# Capacitive_Rain_Sensor.net
KiCad netlist of a schematic drawn in Altium Designer
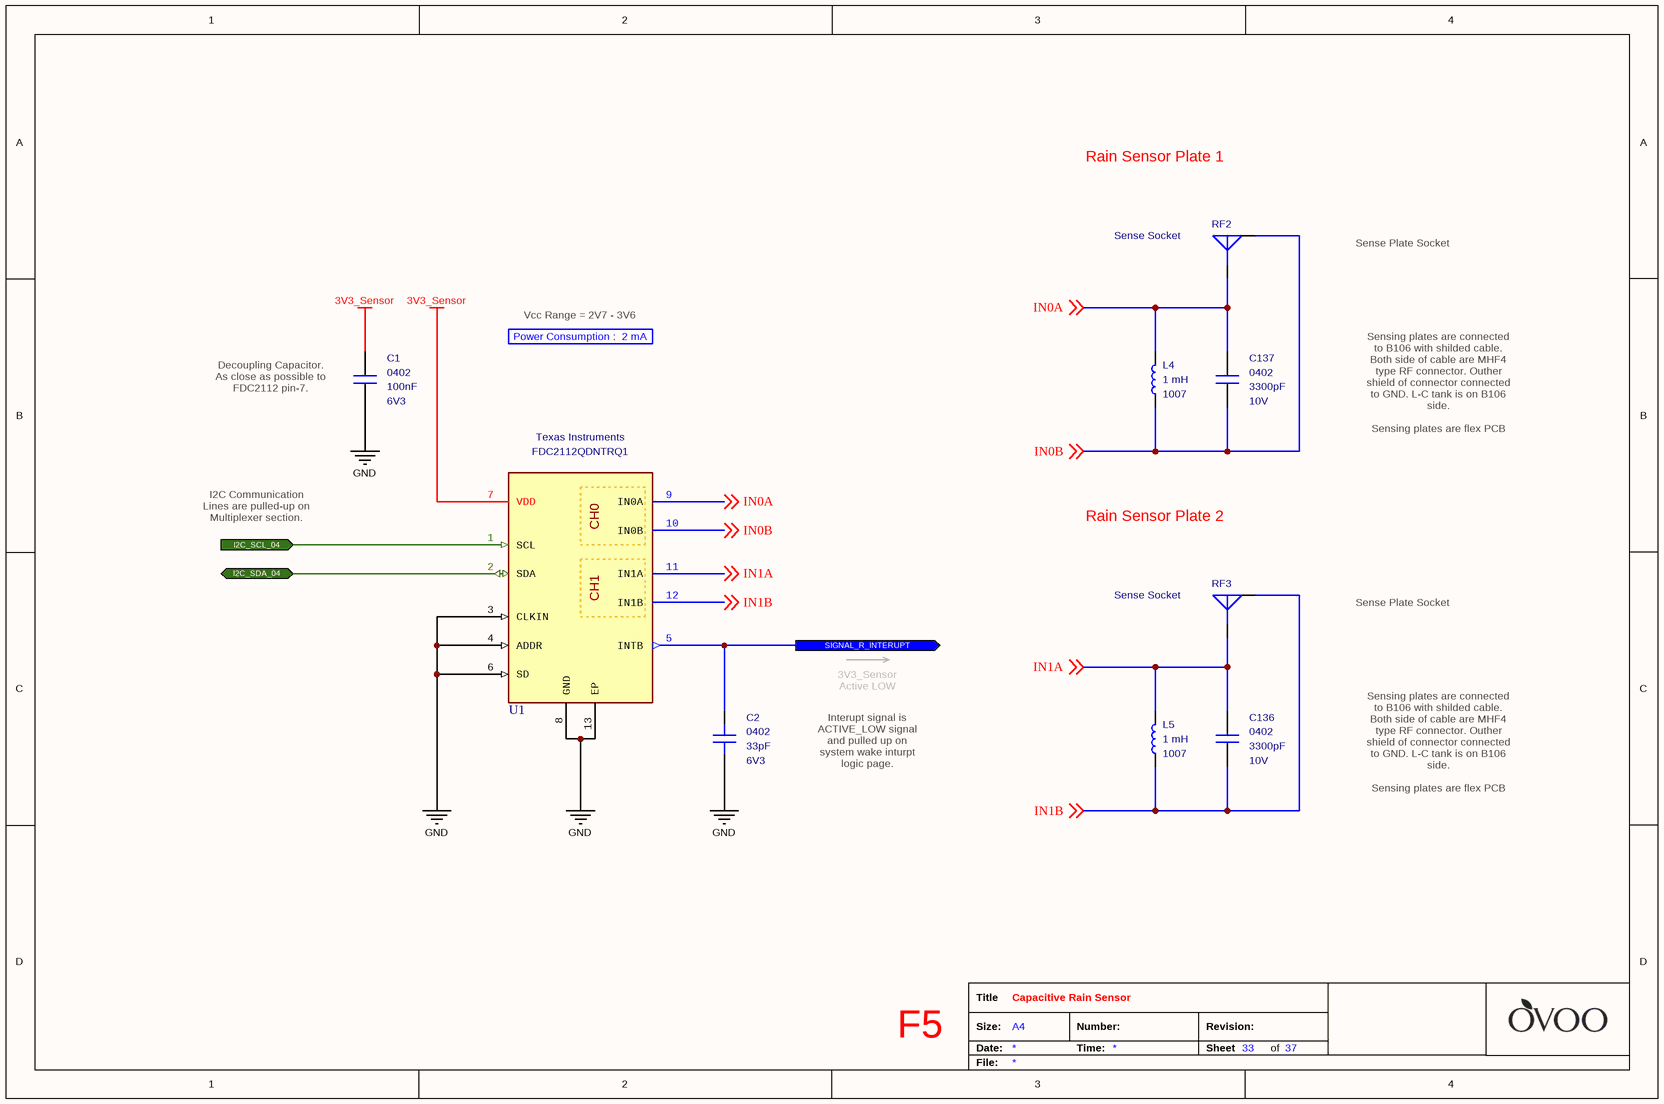
[diagram p0: Capacitive Rain Sensor.SchDoc]

(export (version "E")
  (design (tool "Eeschema 10.0.6"))
  (components
    (comp (ref "C1")
      (value "100nF")
      (footprint "CAPACITOR_0402")
      (description "Capacitor - 100nF [0402-6V3] (Ceramic)")
      (fields
        (field (name "MANUFACTURER_PART_NUMBER") "04026D104KAT4A")
        (field (name "MOUSER_PART_NUMBER") "581-04026D104KAT4A")
        (field (name "CASE") "0402")
        (field (name "VOLTAGE") "6V3")
      )
      (libsource (lib "Ovoo_Schematic") (part "Capacitor - 100nF [0402-6V3]"))
    )
    (comp (ref "C2")
      (value "33pF")
      (footprint "CAPACITOR_0402")
      (description "Capacitor - 33pF [0402] (Ceramic)")
      (fields
        (field (name "MANUFACTURER_PART_NUMBER") "C0402C330J9RACAUTO")
        (field (name "MOUSER_PART_NUMBER") "80-C0402C330J9RAUTO")
        (field (name "CASE") "0402")
        (field (name "VOLTAGE") "6V3")
      )
      (libsource (lib "Ovoo_Schematic") (part "Capacitor - 33pF [0402-6V3]"))
    )
    (comp (ref "C136")
      (value "3300pF")
      (footprint "CAPACITOR_0402")
      (description "Capacitor - 3300pF [0402] (Ceramic)")
      (fields
        (field (name "MANUFACTURER_PART_NUMBER") "VJ0402Y332KXQCW1BC")
        (field (name "MOUSER_PART_NUMBER") "77-VJ0402Y332KXQCBC")
        (field (name "CASE") "0402")
        (field (name "VOLTAGE") "10V")
      )
      (libsource (lib "Ovoo_Schematic") (part "Capacitor - 3300pF [0402-10V)"))
    )
    (comp (ref "C137")
      (value "3300pF")
      (footprint "CAPACITOR_0402")
      (description "Capacitor - 3300pF [0402] (Ceramic)")
      (fields
        (field (name "MANUFACTURER_PART_NUMBER") "VJ0402Y332KXQCW1BC")
        (field (name "MOUSER_PART_NUMBER") "77-VJ0402Y332KXQCBC")
        (field (name "CASE") "0402")
        (field (name "VOLTAGE") "10V")
      )
      (libsource (lib "Ovoo_Schematic") (part "Capacitor - 3300pF [0402-10V)"))
    )
    (comp (ref "L4")
      (value "1 mH")
      (footprint "INDUCTOR_1007")
      (description "Fixed Inductor")
      (fields
        (field (name "MANUFACTURER_PART_NUMBER") "CB2518T102K")
        (field (name "MOUSER_PART_NUMBER") "963-CB2518T102K")
        (field (name "CASE") "1007")
      )
      (libsource (lib "Ovoo_Schematic") (part "Inductor - 1mH [1007]"))
    )
    (comp (ref "L5")
      (value "1 mH")
      (footprint "INDUCTOR_1007")
      (description "Fixed Inductor")
      (fields
        (field (name "MANUFACTURER_PART_NUMBER") "CB2518T102K")
        (field (name "MOUSER_PART_NUMBER") "963-CB2518T102K")
        (field (name "CASE") "1007")
      )
      (libsource (lib "Ovoo_Schematic") (part "Inductor - 1mH [1007]"))
    )
    (comp (ref "RF2")
      (value "Sense Socket")
      (footprint "Connector_IPEX")
      (description "Sense Plate Connection Socket")
      (libsource (lib "Ovoo_Schematic") (part "Connector - MHF"))
    )
    (comp (ref "RF3")
      (value "Sense Socket")
      (footprint "Connector_IPEX")
      (description "Sense Plate Connection Socket")
      (libsource (lib "Ovoo_Schematic") (part "Connector - MHF"))
    )
    (comp (ref "U1")
      (value "Capacitive Sensor")
      (footprint "Texas_DNT")
      (fields
        (field (name "MOUSER PART NUMBER") "595-FDC2112QDNTRQ1")
        (field (name "MANUFACTURER_PART_NUMBER") "FDC2112QDNTRQ1")
        (field (name "MANUFACTURER_NAME") "Texas Instruments")
      )
      (libsource (lib "Ovoo_Schematic") (part "IC - FDC2112QDNTRQ1"))
    )
  )
  (nets
    (net (code "1") (name "/I2C_SCL_04") (class "Default")
      (node (ref "U1") (pin "1") (pinfunction "SCL_1") (pintype "input"))
    )
    (net (code "2") (name "/I2C_SDA_04") (class "Default")
      (node (ref "U1") (pin "2") (pinfunction "SDA_2") (pintype "bidirectional"))
    )
    (net (code "3") (name "/SIGNAL_R_INTERUPT") (class "Default")
      (node (ref "C2") (pin "2") (pinfunction "2_2") (pintype "passive"))
      (node (ref "U1") (pin "5") (pinfunction "INTB_5") (pintype "output"))
    )
    (net (code "4") (name "3V3_Sensor") (class "Default")
      (node (ref "C1") (pin "2") (pinfunction "2_2") (pintype "passive"))
      (node (ref "U1") (pin "7") (pinfunction "VDD_7") (pintype "power_in"))
    )
    (net (code "5") (name "GND") (class "Default")
      (node (ref "C1") (pin "1") (pinfunction "1_1") (pintype "passive"))
      (node (ref "C2") (pin "1") (pinfunction "1_1") (pintype "passive"))
      (node (ref "U1") (pin "13") (pinfunction "EP_13") (pintype "power_in"))
      (node (ref "U1") (pin "3") (pinfunction "CLKIN_3") (pintype "input"))
      (node (ref "U1") (pin "4") (pinfunction "ADDR_4") (pintype "input"))
      (node (ref "U1") (pin "6") (pinfunction "SD_6") (pintype "input"))
      (node (ref "U1") (pin "8") (pinfunction "GND_8") (pintype "power_in"))
    )
    (net (code "6") (name "IN0A") (class "Default")
      (node (ref "C137") (pin "2") (pinfunction "2_2") (pintype "passive"))
      (node (ref "L4") (pin "2") (pinfunction "2_2") (pintype "passive"))
      (node (ref "RF2") (pin "1") (pinfunction "Signal_1") (pintype "passive"))
      (node (ref "U1") (pin "9") (pinfunction "IN0A_9") (pintype "passive"))
    )
    (net (code "7") (name "IN0B") (class "Default")
      (node (ref "C137") (pin "1") (pinfunction "1_1") (pintype "passive"))
      (node (ref "L4") (pin "1") (pinfunction "1_1") (pintype "passive"))
      (node (ref "RF2") (pin "2") (pinfunction "GND_2") (pintype "passive"))
      (node (ref "U1") (pin "10") (pinfunction "IN0B_10") (pintype "passive"))
    )
    (net (code "8") (name "IN1A") (class "Default")
      (node (ref "C136") (pin "2") (pinfunction "2_2") (pintype "passive"))
      (node (ref "L5") (pin "2") (pinfunction "2_2") (pintype "passive"))
      (node (ref "RF3") (pin "1") (pinfunction "Signal_1") (pintype "passive"))
      (node (ref "U1") (pin "11") (pinfunction "IN1A_11") (pintype "passive"))
    )
    (net (code "9") (name "IN1B") (class "Default")
      (node (ref "C136") (pin "1") (pinfunction "1_1") (pintype "passive"))
      (node (ref "L5") (pin "1") (pinfunction "1_1") (pintype "passive"))
      (node (ref "RF3") (pin "2") (pinfunction "GND_2") (pintype "passive"))
      (node (ref "U1") (pin "12") (pinfunction "IN1B_12") (pintype "passive"))
    )
  )
)
